# M5_STACK_STAMP_C3_ISOBUS_JST.net
KiCad netlist of a schematic drawn in EAGLE
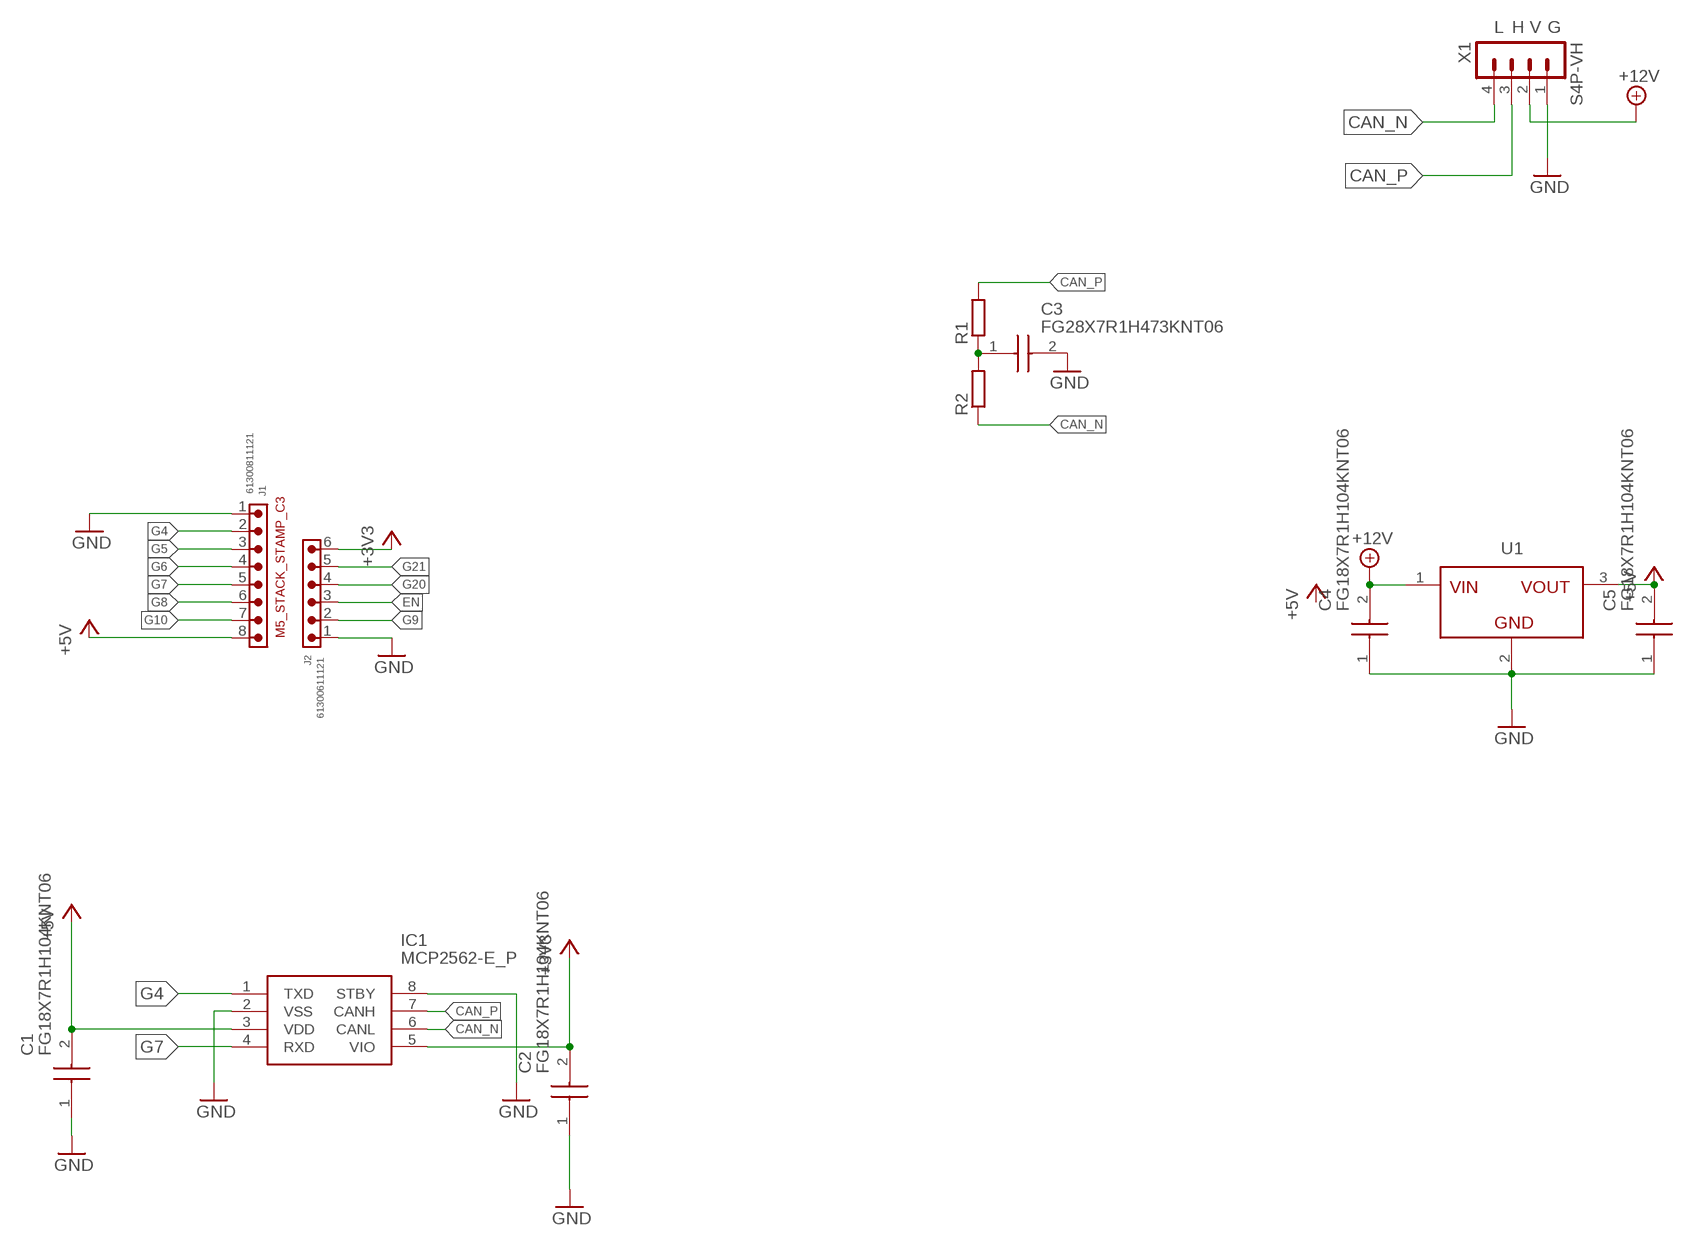
[diagram p0: schematic, sheet 1]

(export (version "E")
  (design (tool "Eeschema 10.0.6"))
  (components
    (comp (ref "C1")
      (value "FG18X7R1H104KNT06")
      (footprint "eagle-import:FG18C0G1H101JNT06")
      (fields (field (name "MOUSER_PART_NUMBER") "810-FG18X7R1H104KNT6"))
      (libsource (lib "eagle-import") (part "FG18X7R1H104KNT06"))
    )
    (comp (ref "C2")
      (value "FG18X7R1H104KNT06")
      (footprint "eagle-import:FG18C0G1H101JNT06")
      (fields (field (name "MOUSER_PART_NUMBER") "810-FG18X7R1H104KNT6"))
      (libsource (lib "eagle-import") (part "FG18X7R1H104KNT06"))
    )
    (comp (ref "C3")
      (value "FG28X7R1H473KNT06")
      (footprint "eagle-import:FG28")
      (fields (field (name "MOUSER_PART_NUMBER") "810-FG28X7R1H473KNT6"))
      (libsource (lib "eagle-import") (part "FG28X7R1H473KNT06"))
    )
    (comp (ref "C4")
      (value "FG18X7R1H104KNT06")
      (footprint "eagle-import:FG18C0G1H101JNT06")
      (fields (field (name "MOUSER_PART_NUMBER") "810-FG18X7R1H104KNT6"))
      (libsource (lib "eagle-import") (part "FG18X7R1H104KNT06"))
    )
    (comp (ref "C5")
      (value "FG18X7R1H104KNT06")
      (footprint "eagle-import:FG18C0G1H101JNT06")
      (fields (field (name "MOUSER_PART_NUMBER") "810-FG18X7R1H104KNT6"))
      (libsource (lib "eagle-import") (part "FG18X7R1H104KNT06"))
    )
    (comp (ref "IC1")
      (value "MCP2562-E_P")
      (footprint "eagle-import:DIP781W56P254L950H533Q8N")
      (fields
        (field (name "MANUFACTURER_PART_NUMBER") "MCP2562-E/P")
        (field (name "MOUSER_PART_NUMBER") "579-MCP2562-E/P")
      )
      (libsource (lib "eagle-import") (part "MCP2562-E_P"))
    )
    (comp (ref "J1")
      (value "61300811121")
      (footprint "eagle-import:61300811121")
      (libsource (lib "eagle-import") (part "6130XX11121_61300811121"))
    )
    (comp (ref "J2")
      (value "61300611121")
      (footprint "eagle-import:61300611121")
      (libsource (lib "eagle-import") (part "6130XX11121_61300611121"))
    )
    (comp (ref "R1")
      (value "R-EU_0204/7")
      (footprint "eagle-import:0204_7")
      (libsource (lib "eagle-import") (part "R-EU_0204/7"))
    )
    (comp (ref "R2")
      (value "R-EU_0204/7")
      (footprint "eagle-import:0204_7")
      (libsource (lib "eagle-import") (part "R-EU_0204/7"))
    )
    (comp (ref "U$1")
      (value "M5_STACK_STAMP_C3")
      (footprint "eagle-import:M5_STACK_STAMP_C3")
      (libsource (lib "eagle-import") (part "M5_STACK_STAMP_C3"))
    )
    (comp (ref "U1")
      (value "MAGI³C-FDSM_SIP-3_173010542_173XXXX42")
      (footprint "eagle-import:MAGI³C-FDSM_173XXXX42")
      (libsource (lib "eagle-import") (part "MAGI³C-FDSM_SIP-3_173XXXX42_173010542"))
    )
    (comp (ref "X1")
      (value "S4P-VH")
      (footprint "eagle-import:S4P-VH")
      (libsource (lib "eagle-import") (part "S4P-VH"))
    )
  )
  (nets
    (net (code "1") (name "+3V3") (class "Default")
      (node (ref "C2") (pin "2") (pinfunction "2_2") (pintype "bidirectional"))
      (node (ref "IC1") (pin "5") (pinfunction "VIO_5") (pintype "bidirectional"))
      (node (ref "J2") (pin "6") (pinfunction "6_6") (pintype "passive"))
    )
    (net (code "2") (name "+5V") (class "Default")
      (node (ref "C1") (pin "2") (pinfunction "2_2") (pintype "bidirectional"))
      (node (ref "C5") (pin "2") (pinfunction "2_2") (pintype "bidirectional"))
      (node (ref "IC1") (pin "3") (pinfunction "VDD_3") (pintype "bidirectional"))
      (node (ref "J1") (pin "8") (pinfunction "8_8") (pintype "passive"))
      (node (ref "U1") (pin "3") (pinfunction "VOUT_3") (pintype "output"))
    )
    (net (code "3") (name "+12V") (class "Default")
      (node (ref "C4") (pin "2") (pinfunction "2_2") (pintype "bidirectional"))
      (node (ref "U1") (pin "1") (pinfunction "VIN_1") (pintype "input"))
      (node (ref "X1") (pin "2") (pinfunction "2_2") (pintype "passive"))
    )
    (net (code "4") (name "CAN_N") (class "Default")
      (node (ref "IC1") (pin "6") (pinfunction "CANL_6") (pintype "bidirectional"))
      (node (ref "R2") (pin "1") (pinfunction "1_1") (pintype "passive"))
      (node (ref "X1") (pin "4") (pinfunction "4_4") (pintype "passive"))
    )
    (net (code "5") (name "CAN_P") (class "Default")
      (node (ref "IC1") (pin "7") (pinfunction "CANH_7") (pintype "bidirectional"))
      (node (ref "R1") (pin "2") (pinfunction "2_2") (pintype "passive"))
      (node (ref "X1") (pin "3") (pinfunction "3_3") (pintype "passive"))
    )
    (net (code "6") (name "EN") (class "Default")
      (node (ref "J2") (pin "3") (pinfunction "3_3") (pintype "passive"))
    )
    (net (code "7") (name "G4") (class "Default")
      (node (ref "IC1") (pin "1") (pinfunction "TXD_1") (pintype "bidirectional"))
      (node (ref "J1") (pin "2") (pinfunction "2_2") (pintype "passive"))
    )
    (net (code "8") (name "G5") (class "Default")
      (node (ref "J1") (pin "3") (pinfunction "3_3") (pintype "passive"))
    )
    (net (code "9") (name "G6") (class "Default")
      (node (ref "J1") (pin "4") (pinfunction "4_4") (pintype "passive"))
    )
    (net (code "10") (name "G7") (class "Default")
      (node (ref "IC1") (pin "4") (pinfunction "RXD_4") (pintype "bidirectional"))
      (node (ref "J1") (pin "5") (pinfunction "5_5") (pintype "passive"))
    )
    (net (code "11") (name "G8") (class "Default")
      (node (ref "J1") (pin "6") (pinfunction "6_6") (pintype "passive"))
    )
    (net (code "12") (name "G9") (class "Default")
      (node (ref "J2") (pin "2") (pinfunction "2_2") (pintype "passive"))
    )
    (net (code "13") (name "G10") (class "Default")
      (node (ref "J1") (pin "7") (pinfunction "7_7") (pintype "passive"))
    )
    (net (code "14") (name "G20") (class "Default")
      (node (ref "J2") (pin "4") (pinfunction "4_4") (pintype "passive"))
    )
    (net (code "15") (name "G21") (class "Default")
      (node (ref "J2") (pin "5") (pinfunction "5_5") (pintype "passive"))
    )
    (net (code "16") (name "GND") (class "Default")
      (node (ref "C1") (pin "1") (pinfunction "1_1") (pintype "bidirectional"))
      (node (ref "C2") (pin "1") (pinfunction "1_1") (pintype "bidirectional"))
      (node (ref "C3") (pin "2") (pinfunction "2_2") (pintype "bidirectional"))
      (node (ref "C4") (pin "1") (pinfunction "1_1") (pintype "bidirectional"))
      (node (ref "C5") (pin "1") (pinfunction "1_1") (pintype "bidirectional"))
      (node (ref "IC1") (pin "2") (pinfunction "VSS_2") (pintype "bidirectional"))
      (node (ref "IC1") (pin "8") (pinfunction "STBY_8") (pintype "bidirectional"))
      (node (ref "J1") (pin "1") (pinfunction "1_1") (pintype "passive"))
      (node (ref "J2") (pin "1") (pinfunction "1_1") (pintype "passive"))
      (node (ref "U1") (pin "2") (pinfunction "GND_2") (pintype "passive"))
      (node (ref "X1") (pin "1") (pinfunction "1_1") (pintype "passive"))
    )
    (net (code "17") (name "Net-(C3-Pad1)") (class "Default")
      (node (ref "C3") (pin "1") (pinfunction "1_1") (pintype "bidirectional"))
      (node (ref "R1") (pin "1") (pinfunction "1_1") (pintype "passive"))
      (node (ref "R2") (pin "2") (pinfunction "2_2") (pintype "passive"))
    )
  )
)
